# SCH_orbital_shaker_front_panel_v2_2022-0.net
KiCad netlist of a schematic drawn in EasyEDA
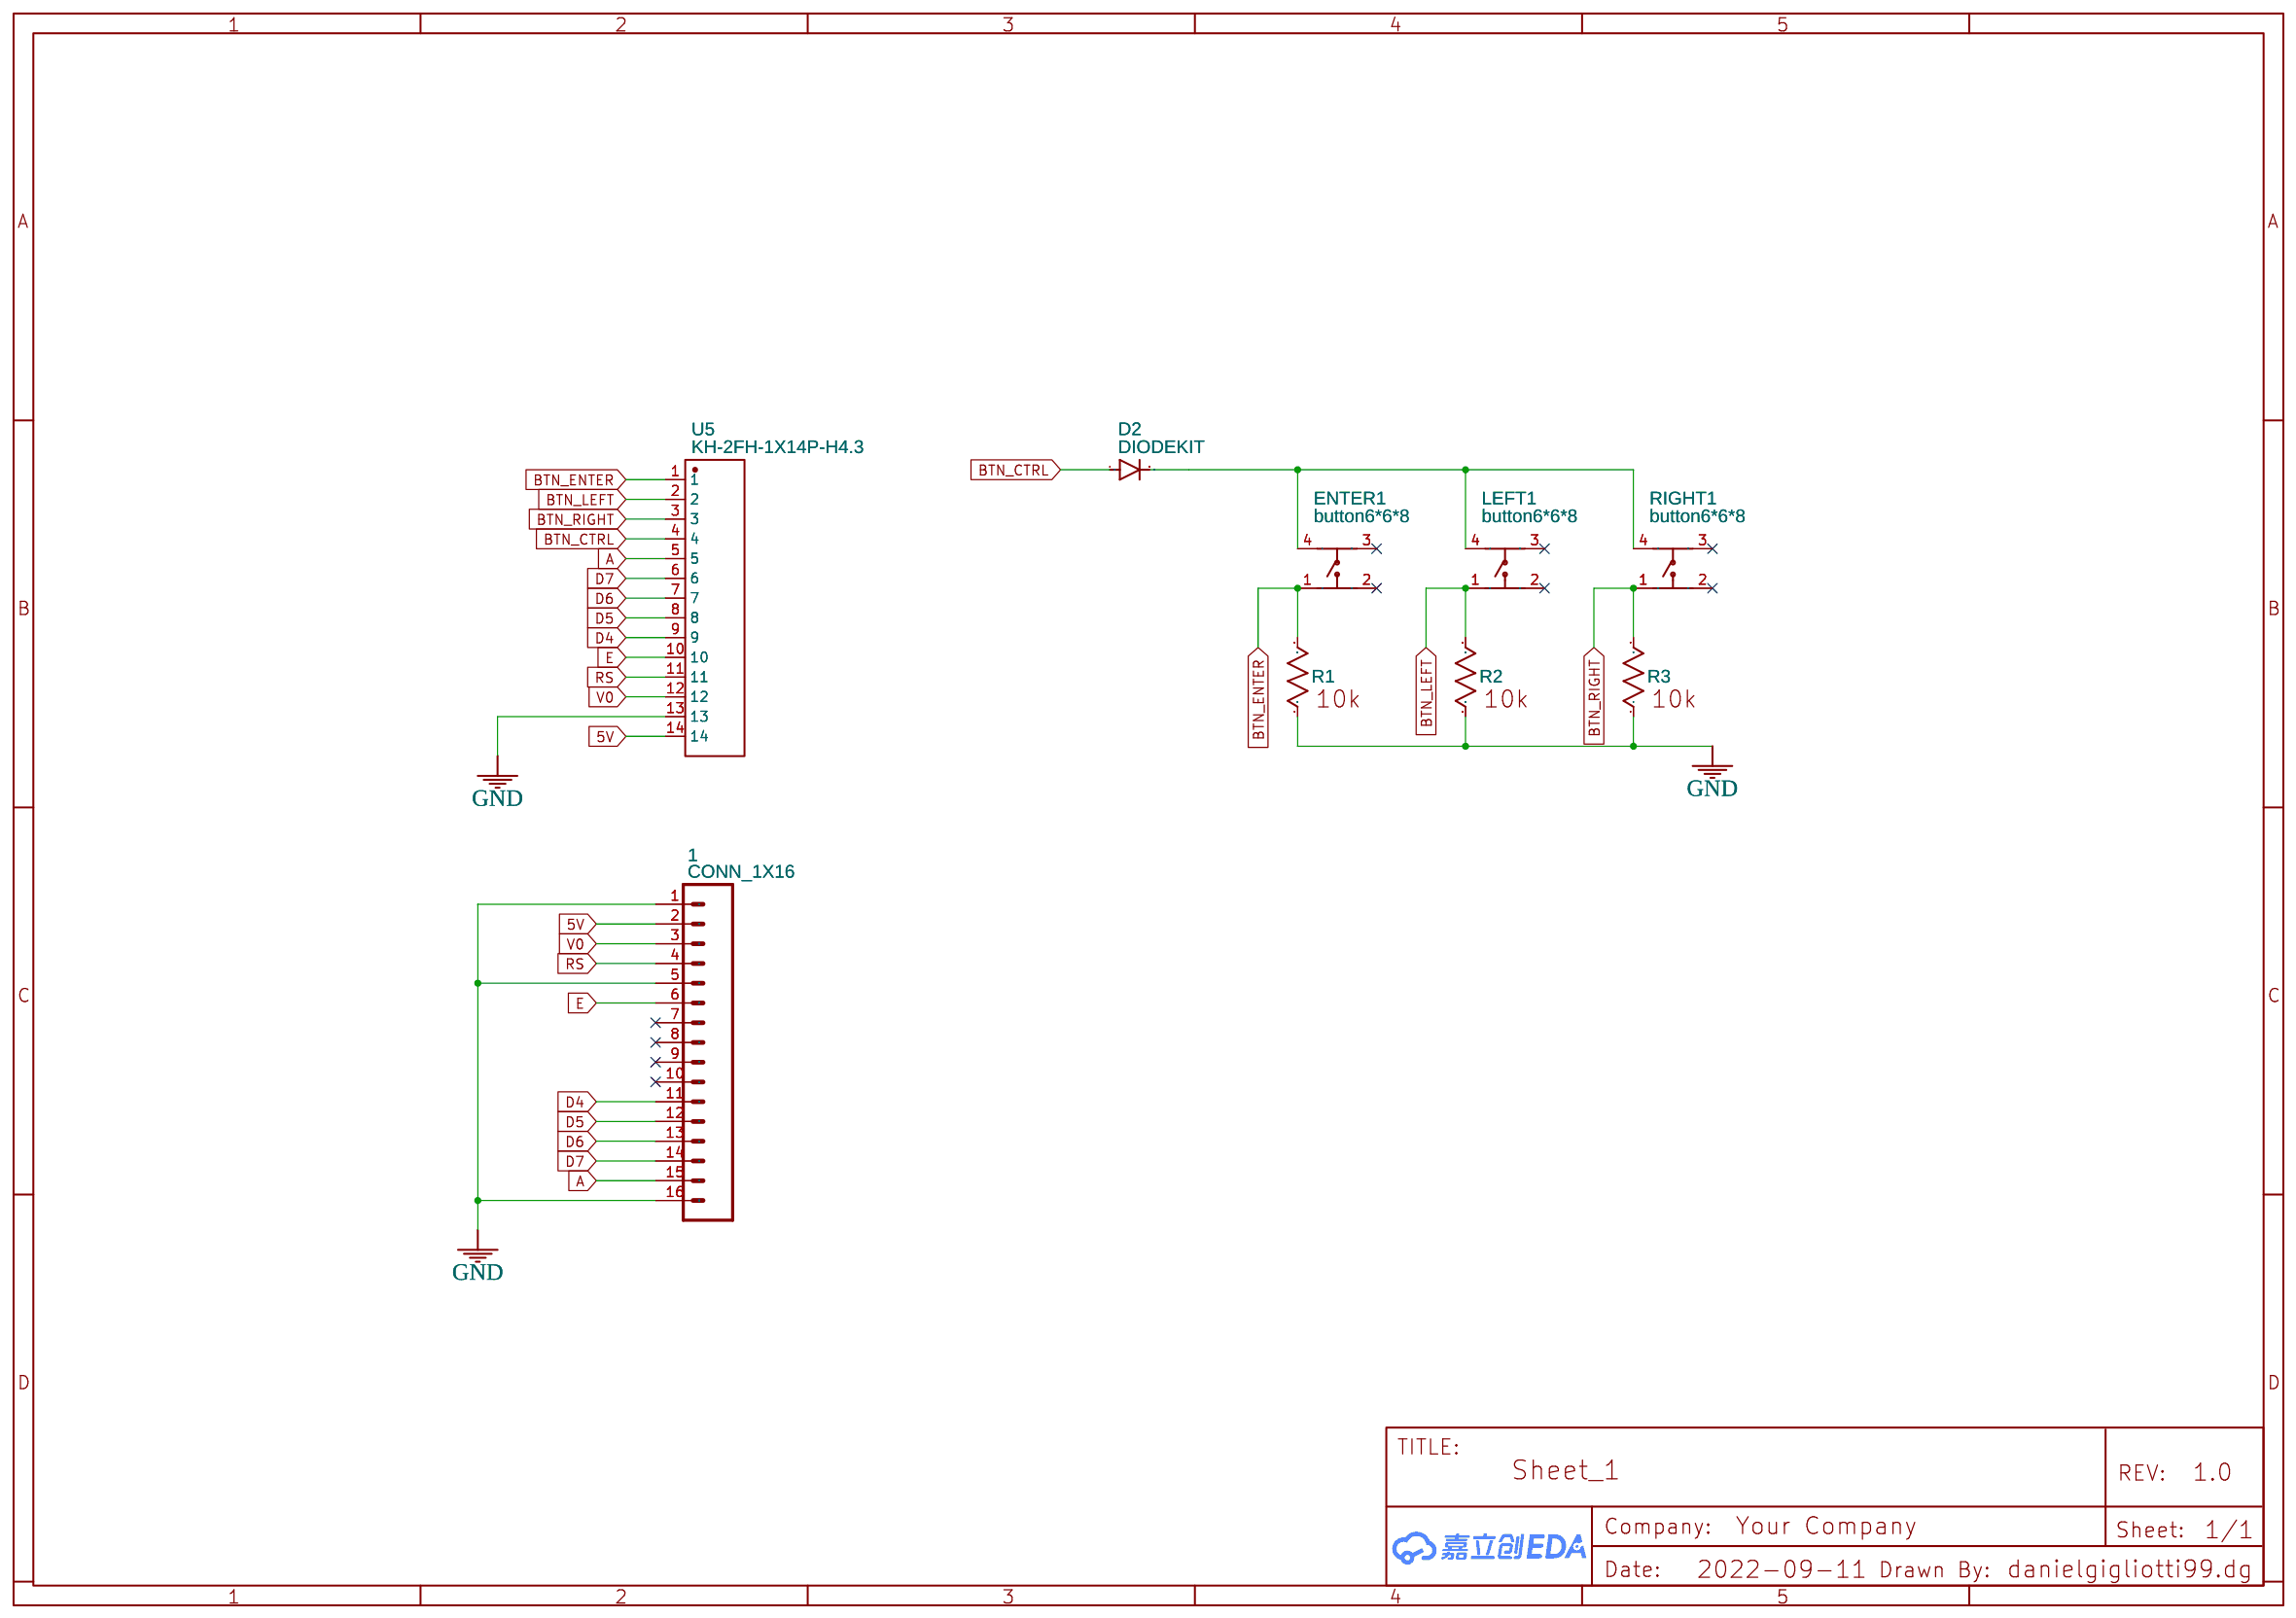
[diagram p0: schematic sheet]

(export (version "E")
  (design (tool "Eeschema 10.0.6"))
  (components
    (comp (ref "1") (value "CONN_1X16") (libsource (lib "") (part "CONN_1X16")))
    (comp (ref "D2") (value "DIODEKIT") (libsource (lib "") (part "DIODEKIT")))
    (comp (ref "ENTER1")
      (value "button6*6*8")
      (fields (field (name "BOM_Supplier Part") "C59982"))
      (libsource (lib "") (part "button6*6*8_1"))
    )
    (comp (ref "LEFT1")
      (value "button6*6*8")
      (fields (field (name "BOM_Supplier Part") "C59982"))
      (libsource (lib "") (part "button6*6*8_2"))
    )
    (comp (ref "R1") (value "1k") (libsource (lib "") (part "1K Resistor")))
    (comp (ref "R2") (value "1k") (libsource (lib "") (part "1K Resistor")))
    (comp (ref "R3") (value "1k") (libsource (lib "") (part "1K Resistor")))
    (comp (ref "RIGHT1")
      (value "button6*6*8")
      (fields (field (name "BOM_Supplier Part") "C59982"))
      (libsource (lib "") (part "button6*6*8"))
    )
    (comp (ref "U5")
      (value "KH-2FH-1X14P-H4.3")
      (fields (field (name "BOM_Supplier Part") "C2938436"))
      (libsource (lib "") (part "KH-2FH-1X14P-H4.3"))
    )
  )
  (nets
    (net (code "1") (name "5V") (class "Default")
      (node (ref "1") (pin "2") (pinfunction "2_2") (pintype "bidirectional"))
      (node (ref "U5") (pin "14") (pinfunction "14_14") (pintype "unspecified"))
    )
    (net (code "2") (name "A") (class "Default")
      (node (ref "1") (pin "15") (pinfunction "15_15") (pintype "bidirectional"))
      (node (ref "U5") (pin "5") (pinfunction "5_5") (pintype "unspecified"))
    )
    (net (code "3") (name "BTN_CTRL") (class "Default")
      (node (ref "D2") (pin "A") (pinfunction "A_A") (pintype "bidirectional"))
      (node (ref "U5") (pin "4") (pinfunction "4_4") (pintype "unspecified"))
    )
    (net (code "4") (name "BTN_ENTER") (class "Default")
      (node (ref "ENTER1") (pin "1") (pinfunction "1_1") (pintype "unspecified"))
      (node (ref "R1") (pin "2") (pinfunction "2_2") (pintype "unspecified"))
      (node (ref "U5") (pin "1") (pinfunction "1_1") (pintype "unspecified"))
    )
    (net (code "5") (name "BTN_LEFT") (class "Default")
      (node (ref "LEFT1") (pin "1") (pinfunction "1_1") (pintype "unspecified"))
      (node (ref "R2") (pin "2") (pinfunction "2_2") (pintype "unspecified"))
      (node (ref "U5") (pin "2") (pinfunction "2_2") (pintype "unspecified"))
    )
    (net (code "6") (name "BTN_RIGHT") (class "Default")
      (node (ref "R3") (pin "2") (pinfunction "2_2") (pintype "unspecified"))
      (node (ref "RIGHT1") (pin "1") (pinfunction "1_1") (pintype "unspecified"))
      (node (ref "U5") (pin "3") (pinfunction "3_3") (pintype "unspecified"))
    )
    (net (code "7") (name "D4") (class "Default")
      (node (ref "1") (pin "11") (pinfunction "11_11") (pintype "bidirectional"))
      (node (ref "U5") (pin "9") (pinfunction "9_9") (pintype "unspecified"))
    )
    (net (code "8") (name "D5") (class "Default")
      (node (ref "1") (pin "12") (pinfunction "12_12") (pintype "bidirectional"))
      (node (ref "U5") (pin "8") (pinfunction "8_8") (pintype "unspecified"))
    )
    (net (code "9") (name "D6") (class "Default")
      (node (ref "1") (pin "13") (pinfunction "13_13") (pintype "bidirectional"))
      (node (ref "U5") (pin "7") (pinfunction "7_7") (pintype "unspecified"))
    )
    (net (code "10") (name "D7") (class "Default")
      (node (ref "1") (pin "14") (pinfunction "14_14") (pintype "bidirectional"))
      (node (ref "U5") (pin "6") (pinfunction "6_6") (pintype "unspecified"))
    )
    (net (code "11") (name "E") (class "Default")
      (node (ref "1") (pin "6") (pinfunction "6_6") (pintype "bidirectional"))
      (node (ref "U5") (pin "10") (pinfunction "10_10") (pintype "unspecified"))
    )
    (net (code "12") (name "GND") (class "Default")
      (node (ref "1") (pin "1") (pinfunction "1_1") (pintype "bidirectional"))
      (node (ref "1") (pin "16") (pinfunction "16_16") (pintype "bidirectional"))
      (node (ref "1") (pin "5") (pinfunction "5_5") (pintype "bidirectional"))
      (node (ref "R1") (pin "1") (pinfunction "1_1") (pintype "unspecified"))
      (node (ref "R2") (pin "1") (pinfunction "1_1") (pintype "unspecified"))
      (node (ref "R3") (pin "1") (pinfunction "1_1") (pintype "unspecified"))
      (node (ref "U5") (pin "13") (pinfunction "13_13") (pintype "unspecified"))
    )
    (net (code "13") (name "Net-(D2-PadC)") (class "Default")
      (node (ref "D2") (pin "C") (pinfunction "C_C") (pintype "bidirectional"))
      (node (ref "ENTER1") (pin "4") (pinfunction "4_4") (pintype "unspecified"))
      (node (ref "LEFT1") (pin "4") (pinfunction "4_4") (pintype "unspecified"))
      (node (ref "RIGHT1") (pin "4") (pinfunction "4_4") (pintype "unspecified"))
    )
    (net (code "14") (name "RS") (class "Default")
      (node (ref "1") (pin "4") (pinfunction "4_4") (pintype "bidirectional"))
      (node (ref "U5") (pin "11") (pinfunction "11_11") (pintype "unspecified"))
    )
    (net (code "15") (name "V0") (class "Default")
      (node (ref "1") (pin "3") (pinfunction "3_3") (pintype "bidirectional"))
      (node (ref "U5") (pin "12") (pinfunction "12_12") (pintype "unspecified"))
    )
    (net (code "16") (name "unconnected-(1-Pad7)") (class "Default")
      (node (ref "1") (pin "7") (pinfunction "7_7") (pintype "bidirectional+no_connect"))
    )
    (net (code "17") (name "unconnected-(1-Pad8)") (class "Default")
      (node (ref "1") (pin "8") (pinfunction "8_8") (pintype "bidirectional+no_connect"))
    )
    (net (code "18") (name "unconnected-(1-Pad9)") (class "Default")
      (node (ref "1") (pin "9") (pinfunction "9_9") (pintype "bidirectional+no_connect"))
    )
    (net (code "19") (name "unconnected-(1-Pad10)") (class "Default")
      (node (ref "1") (pin "10") (pinfunction "10_10") (pintype "bidirectional+no_connect"))
    )
    (net (code "20") (name "unconnected-(ENTER1-Pad2)") (class "Default")
      (node (ref "ENTER1") (pin "2") (pinfunction "2_2") (pintype "unspecified+no_connect"))
    )
    (net (code "21") (name "unconnected-(ENTER1-Pad3)") (class "Default")
      (node (ref "ENTER1") (pin "3") (pinfunction "3_3") (pintype "unspecified+no_connect"))
    )
    (net (code "22") (name "unconnected-(LEFT1-Pad2)") (class "Default")
      (node (ref "LEFT1") (pin "2") (pinfunction "2_2") (pintype "unspecified+no_connect"))
    )
    (net (code "23") (name "unconnected-(LEFT1-Pad3)") (class "Default")
      (node (ref "LEFT1") (pin "3") (pinfunction "3_3") (pintype "unspecified+no_connect"))
    )
    (net (code "24") (name "unconnected-(RIGHT1-Pad2)") (class "Default")
      (node (ref "RIGHT1") (pin "2") (pinfunction "2_2") (pintype "unspecified+no_connect"))
    )
    (net (code "25") (name "unconnected-(RIGHT1-Pad3)") (class "Default")
      (node (ref "RIGHT1") (pin "3") (pinfunction "3_3") (pintype "unspecified+no_connect"))
    )
  )
)
